# ad8130.net
KiCad netlist of a schematic drawn in Altium Designer
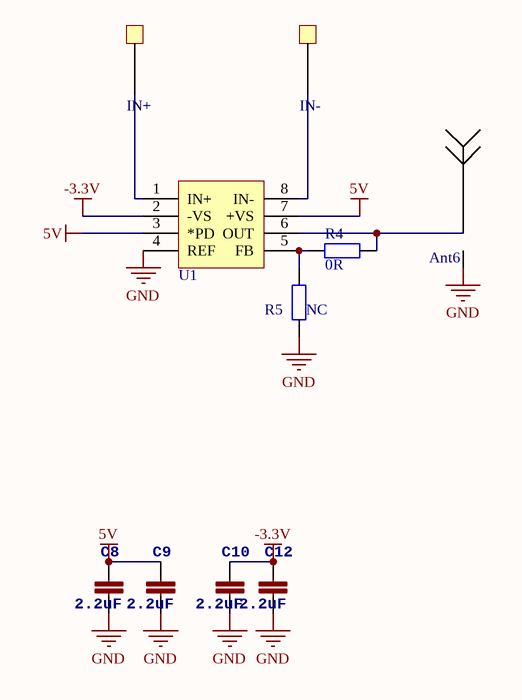
[diagram p0: ad8130.SchDoc]

(export (version "E")
  (design (tool "Eeschema 10.0.6"))
  (components
    (comp (ref "Ant6") (value "Antenna") (footprint "SMA-HOLE") (libsource (lib "F4SDR") (part "Antenna")))
    (comp (ref "C8")
      (value "2.2uF")
      (footprint "0603")
      (description "<b>Capacitor</b>\nStandard 0603 ceramic capacitor, and 0.1\" leaded capacitor.")
      (fields (field (name "PARTNO") "CC0402ZRY5V7BB104"))
      (libsource (lib "pixhawk2") (part "CAP0402-CAP"))
    )
    (comp (ref "C9")
      (value "2.2uF")
      (footprint "0603")
      (description "<b>Capacitor</b>\nStandard 0603 ceramic capacitor, and 0.1\" leaded capacitor.")
      (fields (field (name "PARTNO") "CC0402ZRY5V7BB104"))
      (libsource (lib "pixhawk2") (part "CAP0402-CAP"))
    )
    (comp (ref "C10")
      (value "2.2uF")
      (footprint "0603")
      (description "<b>Capacitor</b>\nStandard 0603 ceramic capacitor, and 0.1\" leaded capacitor.")
      (fields (field (name "PARTNO") "CC0402ZRY5V7BB104"))
      (libsource (lib "pixhawk2") (part "CAP0402-CAP"))
    )
    (comp (ref "C12")
      (value "2.2uF")
      (footprint "0603")
      (description "<b>Capacitor</b>\nStandard 0603 ceramic capacitor, and 0.1\" leaded capacitor.")
      (fields (field (name "PARTNO") "CC0402ZRY5V7BB104"))
      (libsource (lib "pixhawk2") (part "CAP0402-CAP"))
    )
    (comp (ref "IN+") (value "TestPad") (footprint "TestPad") (libsource (lib "sch") (part "TestPad")))
    (comp (ref "IN-") (value "TestPad") (footprint "TestPad") (libsource (lib "sch") (part "TestPad")))
    (comp (ref "R4")
      (value "0R")
      (footprint "0402")
      (description "Resistor")
      (fields (field (name "PUBLISHER") "Altium Limited"))
      (libsource (lib "Miscellaneous Devices") (part "Res2"))
    )
    (comp (ref "R5")
      (value "NC")
      (footprint "0402")
      (description "Resistor")
      (fields (field (name "PUBLISHER") "Altium Limited"))
      (libsource (lib "") (part "Res2_1"))
    )
    (comp (ref "U1") (value "AD8130") (footprint "SO8") (libsource (lib "F4SDR") (part "AD8130")))
  )
  (nets
    (net (code "1") (name "-3.3V") (class "Default")
      (node (ref "C10") (pin "2") (pinfunction "2_2") (pintype "passive"))
      (node (ref "C12") (pin "2") (pinfunction "2_2") (pintype "passive"))
      (node (ref "U1") (pin "2") (pinfunction "-VS_2") (pintype "passive"))
    )
    (net (code "2") (name "5V") (class "Default")
      (node (ref "C8") (pin "2") (pinfunction "2_2") (pintype "passive"))
      (node (ref "C9") (pin "2") (pinfunction "2_2") (pintype "passive"))
      (node (ref "U1") (pin "3") (pinfunction "*PD_3") (pintype "passive"))
      (node (ref "U1") (pin "7") (pinfunction "+VS_7") (pintype "passive"))
    )
    (net (code "3") (name "GND") (class "Default")
      (node (ref "Ant6") (pin "GND") (pinfunction "G_GND") (pintype "passive"))
      (node (ref "C10") (pin "1") (pinfunction "1_1") (pintype "passive"))
      (node (ref "C12") (pin "1") (pinfunction "1_1") (pintype "passive"))
      (node (ref "C8") (pin "1") (pinfunction "1_1") (pintype "passive"))
      (node (ref "C9") (pin "1") (pinfunction "1_1") (pintype "passive"))
      (node (ref "R5") (pin "1") (pinfunction "1_1") (pintype "passive"))
      (node (ref "U1") (pin "4") (pinfunction "REF_4") (pintype "passive"))
    )
    (net (code "4") (name "Net-(IN+-3)") (class "Default")
      (node (ref "IN+") (pin "1") (pinfunction "3_1") (pintype "passive"))
      (node (ref "U1") (pin "1") (pinfunction "IN+_1") (pintype "passive"))
    )
    (net (code "5") (name "Net-(IN--3)") (class "Default")
      (node (ref "IN-") (pin "1") (pinfunction "3_1") (pintype "passive"))
      (node (ref "U1") (pin "8") (pinfunction "IN-_8") (pintype "passive"))
    )
    (net (code "6") (name "Net-(U1-FB)") (class "Default")
      (node (ref "R4") (pin "2") (pinfunction "2_2") (pintype "passive"))
      (node (ref "R5") (pin "2") (pinfunction "2_2") (pintype "passive"))
      (node (ref "U1") (pin "5") (pinfunction "FB_5") (pintype "passive"))
    )
    (net (code "7") (name "Net-(U1-OUT)") (class "Default")
      (node (ref "Ant6") (pin "1") (pinfunction "1_1") (pintype "passive"))
      (node (ref "R4") (pin "1") (pinfunction "1_1") (pintype "passive"))
      (node (ref "U1") (pin "6") (pinfunction "OUT_6") (pintype "passive"))
    )
  )
)
